# BreaV4B.net
KiCad netlist of a schematic drawn in EAGLE
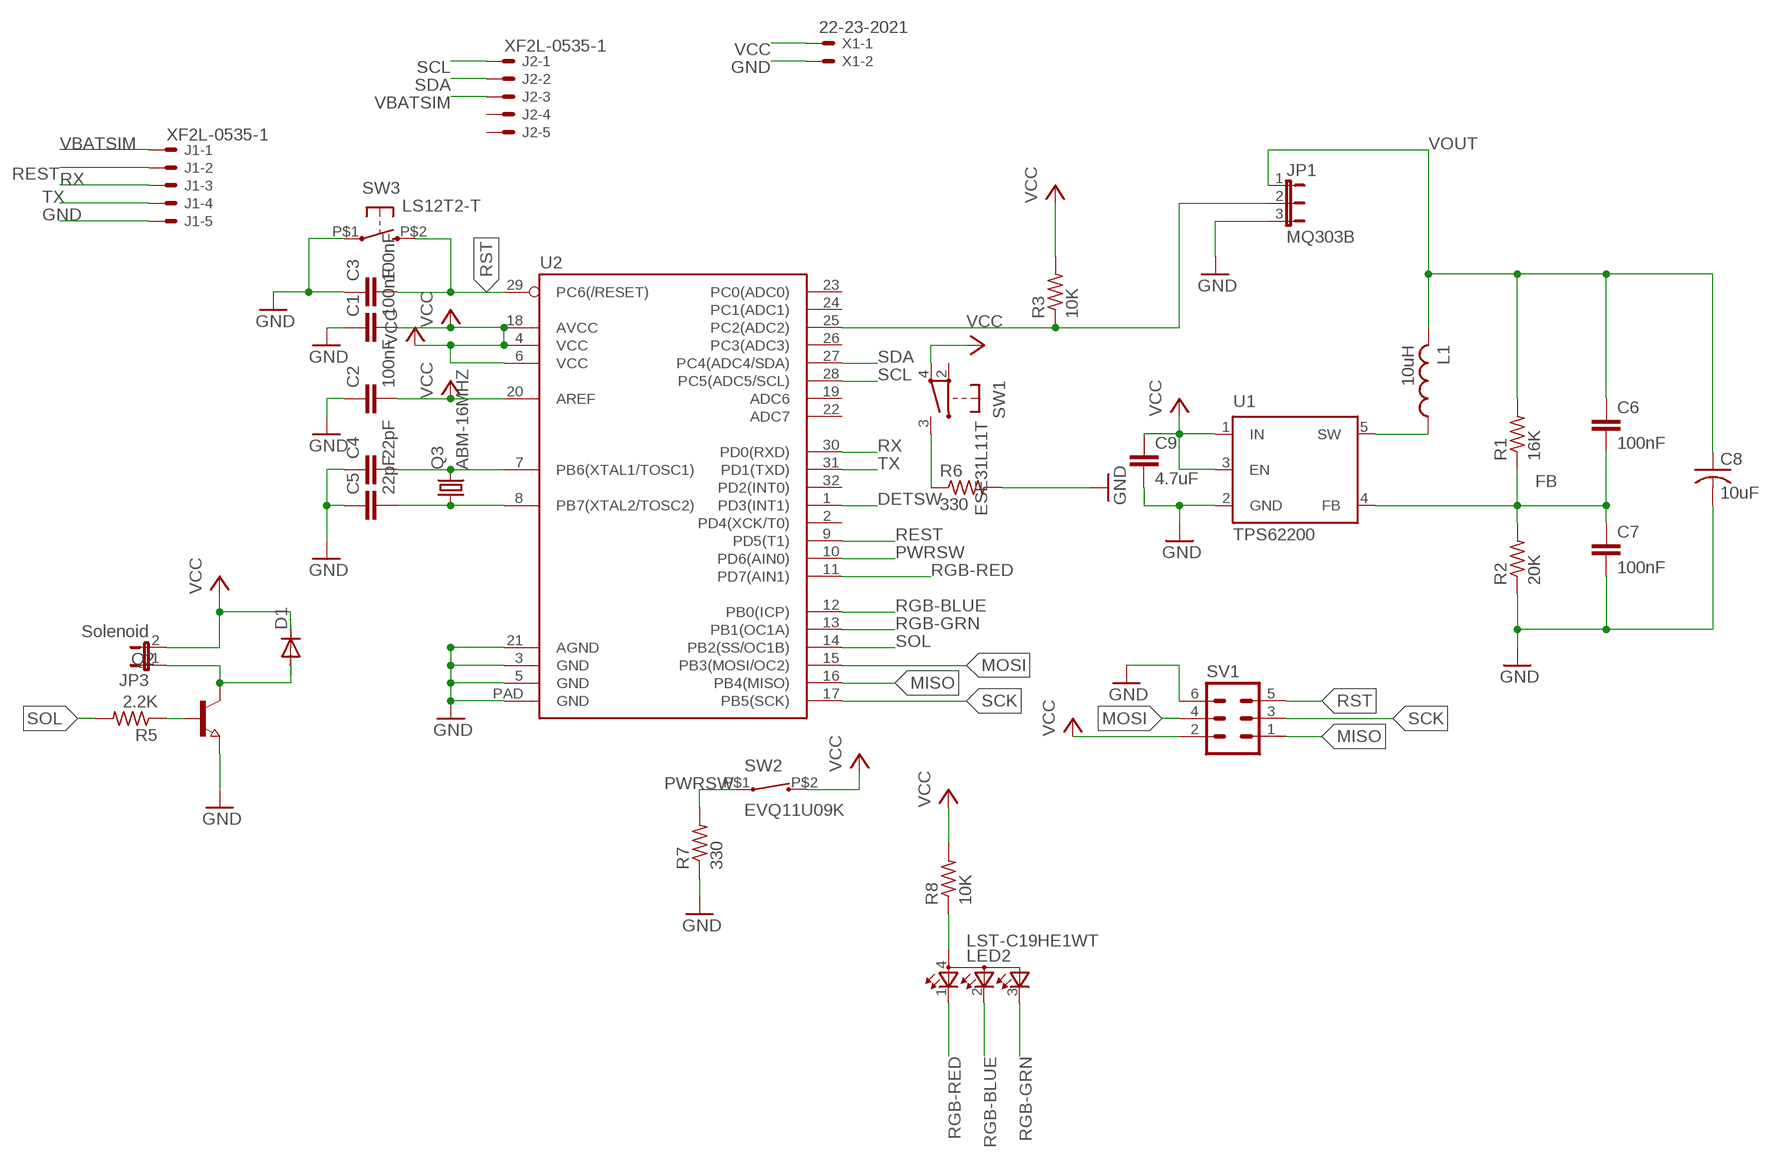
[diagram p0: schematic, sheet 1]

(export (version "E")
  (design (tool "Eeschema 10.0.6"))
  (components
    (comp (ref "C1")
      (value "100nF")
      (footprint "eagle-import:C0603")
      (libsource (lib "eagle-import") (part "C-EUC0603"))
    )
    (comp (ref "C2")
      (value "100nF")
      (footprint "eagle-import:C0603")
      (libsource (lib "eagle-import") (part "C-EUC0603"))
    )
    (comp (ref "C3")
      (value "100nF")
      (footprint "eagle-import:C0603")
      (libsource (lib "eagle-import") (part "C-EUC0603"))
    )
    (comp (ref "C4")
      (value "22pF")
      (footprint "eagle-import:C0603")
      (libsource (lib "eagle-import") (part "C-EUC0603"))
    )
    (comp (ref "C5")
      (value "22pF")
      (footprint "eagle-import:C0603")
      (libsource (lib "eagle-import") (part "C-EUC0603"))
    )
    (comp (ref "C6")
      (value "100nF")
      (footprint "eagle-import:C0402")
      (libsource (lib "eagle-import") (part "C-EUC0402"))
    )
    (comp (ref "C7")
      (value "100nF")
      (footprint "eagle-import:C0402")
      (libsource (lib "eagle-import") (part "C-EUC0402"))
    )
    (comp (ref "C8")
      (value "10uF")
      (footprint "eagle-import:C0805K")
      (libsource (lib "eagle-import") (part "C-USC0805K"))
    )
    (comp (ref "C9")
      (value "4.7uF")
      (footprint "eagle-import:C0402")
      (libsource (lib "eagle-import") (part "C-EUC0402"))
    )
    (comp (ref "D1")
      (value "DIODE-SOD123")
      (footprint "eagle-import:SOD123")
      (libsource (lib "eagle-import") (part "DIODE-SOD123"))
    )
    (comp (ref "J1")
      (value "XF2L-0535-1")
      (footprint "eagle-import:XF2L-0535-1")
      (libsource (lib "eagle-import") (part "XF2-05?35-1L"))
    )
    (comp (ref "J2")
      (value "XF2L-0535-1")
      (footprint "eagle-import:XF2L-0535-1")
      (libsource (lib "eagle-import") (part "XF2-05?35-1L"))
    )
    (comp (ref "JP1")
      (value "MQ303B")
      (footprint "eagle-import:JP2")
      (libsource (lib "eagle-import") (part "JP2E"))
    )
    (comp (ref "JP3")
      (value "Solenoid")
      (footprint "eagle-import:JP1")
      (libsource (lib "eagle-import") (part "JP1E"))
    )
    (comp (ref "L1")
      (value "10uH")
      (footprint "eagle-import:L2825P")
      (libsource (lib "eagle-import") (part "L-USL2825P"))
    )
    (comp (ref "LED2")
      (value "LST-C19HE1WT")
      (footprint "eagle-import:LST-C19HE1WT")
      (libsource (lib "eagle-import") (part "LST-C19HE1WT"))
    )
    (comp (ref "Q2")
      (value "NPN-TRANSISTOR_SOT23")
      (footprint "eagle-import:SOT23")
      (libsource (lib "eagle-import") (part "NPN-TRANSISTOR_SOT23"))
    )
    (comp (ref "Q3")
      (value "ABM-16MHZ")
      (footprint "eagle-import:ABM-16MHZ")
      (libsource (lib "eagle-import") (part "ABM-16MHZ"))
    )
    (comp (ref "R1")
      (value "16K")
      (footprint "eagle-import:R0402")
      (libsource (lib "eagle-import") (part "R-US_R0402"))
    )
    (comp (ref "R2")
      (value "20K")
      (footprint "eagle-import:R0402")
      (libsource (lib "eagle-import") (part "R-US_R0402"))
    )
    (comp (ref "R3")
      (value "10K")
      (footprint "eagle-import:R0402")
      (libsource (lib "eagle-import") (part "R-US_R0402"))
    )
    (comp (ref "R5")
      (value "2.2K")
      (footprint "eagle-import:R0402")
      (libsource (lib "eagle-import") (part "R-US_R0402"))
    )
    (comp (ref "R6")
      (value "330")
      (footprint "eagle-import:R0402")
      (libsource (lib "eagle-import") (part "R-US_R0402"))
    )
    (comp (ref "R7")
      (value "330")
      (footprint "eagle-import:R0402")
      (libsource (lib "eagle-import") (part "R-US_R0402"))
    )
    (comp (ref "R8")
      (value "10K")
      (footprint "eagle-import:R0402")
      (libsource (lib "eagle-import") (part "R-US_R0402"))
    )
    (comp (ref "SV1")
      (value "MA03-2")
      (footprint "eagle-import:MA03-2")
      (libsource (lib "eagle-import") (part "MA03-2"))
    )
    (comp (ref "SW1")
      (value "ESE31L11T")
      (footprint "eagle-import:SWITCH")
      (libsource (lib "eagle-import") (part "ESE31L11T"))
    )
    (comp (ref "SW2")
      (value "EVQ11U09K")
      (footprint "eagle-import:EVQ11U-09K")
      (libsource (lib "eagle-import") (part "EVQ11U09K"))
    )
    (comp (ref "SW3")
      (value "LS12T2-T")
      (footprint "eagle-import:LS12T2-T")
      (libsource (lib "eagle-import") (part "LS12T2-T"))
    )
    (comp (ref "U1")
      (value "TPS62200")
      (footprint "eagle-import:TPS62200")
      (libsource (lib "eagle-import") (part "TPS62200"))
    )
    (comp (ref "U2")
      (value "ATMEGA328P_MLFMLF32")
      (footprint "eagle-import:MLF32-PAD")
      (libsource (lib "eagle-import") (part "ATMEGA328P_MLFMLF32"))
    )
    (comp (ref "X1")
      (value "22-23-2021")
      (footprint "eagle-import:22-23-2021")
      (fields (field (name "MF") "MOLEX"))
      (libsource (lib "eagle-import") (part "22-23-2021"))
    )
  )
  (nets
    (net (code "1") (name "/DETSW") (class "Default")
      (node (ref "R6") (pin "1") (pinfunction "1_1") (pintype "passive"))
      (node (ref "SW1") (pin "3") (pinfunction "1_3") (pintype "passive"))
      (node (ref "U2") (pin "1") (pinfunction "PD3(INT1)_1") (pintype "bidirectional"))
    )
    (net (code "2") (name "/FB") (class "Default")
      (node (ref "C6") (pin "2") (pinfunction "2_2") (pintype "passive"))
      (node (ref "C7") (pin "1") (pinfunction "1_1") (pintype "passive"))
      (node (ref "R1") (pin "1") (pinfunction "1_1") (pintype "passive"))
      (node (ref "R2") (pin "2") (pinfunction "2_2") (pintype "passive"))
      (node (ref "U1") (pin "4") (pinfunction "FB_4") (pintype "passive"))
    )
    (net (code "3") (name "/PWRSW") (class "Default")
      (node (ref "R7") (pin "2") (pinfunction "2_2") (pintype "passive"))
      (node (ref "SW2") (pin "P$1") (pinfunction "1_P$1") (pintype "passive"))
      (node (ref "U2") (pin "10") (pinfunction "PD6(AIN0)_10") (pintype "bidirectional"))
    )
    (net (code "4") (name "/REST") (class "Default")
      (node (ref "J1") (pin "2") (pinfunction "MS_2") (pintype "passive"))
      (node (ref "U2") (pin "9") (pinfunction "PD5(T1)_9") (pintype "bidirectional"))
    )
    (net (code "5") (name "/RGB-BLUE") (class "Default")
      (node (ref "LED2") (pin "2") (pinfunction "CGREEN_2") (pintype "passive"))
      (node (ref "U2") (pin "12") (pinfunction "PB0(ICP)_12") (pintype "bidirectional"))
    )
    (net (code "6") (name "/RGB-GRN") (class "Default")
      (node (ref "LED2") (pin "3") (pinfunction "CBLUE_3") (pintype "passive"))
      (node (ref "U2") (pin "13") (pinfunction "PB1(OC1A)_13") (pintype "bidirectional"))
    )
    (net (code "7") (name "/RGB-RED") (class "Default")
      (node (ref "LED2") (pin "1") (pinfunction "CRED_1") (pintype "passive"))
      (node (ref "U2") (pin "11") (pinfunction "PD7(AIN1)_11") (pintype "bidirectional"))
    )
    (net (code "8") (name "/RX") (class "Default")
      (node (ref "J1") (pin "3") (pinfunction "MS_3") (pintype "passive"))
      (node (ref "U2") (pin "30") (pinfunction "PD0(RXD)_30") (pintype "bidirectional"))
    )
    (net (code "9") (name "/SCL") (class "Default")
      (node (ref "J2") (pin "1") (pinfunction "MSV_1") (pintype "passive"))
      (node (ref "U2") (pin "28") (pinfunction "PC5(ADC5/SCL)_28") (pintype "bidirectional"))
    )
    (net (code "10") (name "/SDA") (class "Default")
      (node (ref "J2") (pin "2") (pinfunction "MS_2") (pintype "passive"))
      (node (ref "U2") (pin "27") (pinfunction "PC4(ADC4/SDA)_27") (pintype "bidirectional"))
    )
    (net (code "11") (name "/TX") (class "Default")
      (node (ref "J1") (pin "4") (pinfunction "MS_4") (pintype "passive"))
      (node (ref "U2") (pin "31") (pinfunction "PD1(TXD)_31") (pintype "bidirectional"))
    )
    (net (code "12") (name "/VBATSIM") (class "Default")
      (node (ref "J1") (pin "1") (pinfunction "MSV_1") (pintype "passive"))
      (node (ref "J2") (pin "3") (pinfunction "MS_3") (pintype "passive"))
    )
    (net (code "13") (name "/VOUT") (class "Default")
      (node (ref "C6") (pin "1") (pinfunction "1_1") (pintype "passive"))
      (node (ref "C8") (pin "1") (pinfunction "1_1") (pintype "passive"))
      (node (ref "JP1") (pin "1") (pinfunction "1_1") (pintype "passive"))
      (node (ref "L1") (pin "2") (pinfunction "2_2") (pintype "passive"))
      (node (ref "R1") (pin "2") (pinfunction "2_2") (pintype "passive"))
    )
    (net (code "14") (name "GND") (class "Default")
      (node (ref "C1") (pin "1") (pinfunction "1_1") (pintype "passive"))
      (node (ref "C2") (pin "1") (pinfunction "1_1") (pintype "passive"))
      (node (ref "C3") (pin "1") (pinfunction "1_1") (pintype "passive"))
      (node (ref "C4") (pin "1") (pinfunction "1_1") (pintype "passive"))
      (node (ref "C5") (pin "1") (pinfunction "1_1") (pintype "passive"))
      (node (ref "C7") (pin "2") (pinfunction "2_2") (pintype "passive"))
      (node (ref "C8") (pin "2") (pinfunction "2_2") (pintype "passive"))
      (node (ref "C9") (pin "2") (pinfunction "2_2") (pintype "passive"))
      (node (ref "J1") (pin "5") (pinfunction "MS_5") (pintype "passive"))
      (node (ref "JP1") (pin "3") (pinfunction "3_3") (pintype "passive"))
      (node (ref "Q2") (pin "2") (pinfunction "E_2") (pintype "passive"))
      (node (ref "R2") (pin "1") (pinfunction "1_1") (pintype "passive"))
      (node (ref "R6") (pin "2") (pinfunction "2_2") (pintype "passive"))
      (node (ref "R7") (pin "1") (pinfunction "1_1") (pintype "passive"))
      (node (ref "SV1") (pin "6") (pinfunction "MISO_6") (pintype "passive"))
      (node (ref "SW3") (pin "P$1") (pinfunction "S1_P$1") (pintype "passive"))
      (node (ref "U1") (pin "2") (pinfunction "GND_2") (pintype "power_in"))
      (node (ref "U2") (pin "21") (pinfunction "AGND_21") (pintype "bidirectional"))
      (node (ref "U2") (pin "3") (pinfunction "GND_3") (pintype "bidirectional"))
      (node (ref "U2") (pin "5") (pinfunction "GND_5") (pintype "bidirectional"))
      (node (ref "U2") (pin "PAD") (pinfunction "GND_PAD") (pintype "bidirectional"))
      (node (ref "X1") (pin "2") (pinfunction "S_2") (pintype "passive"))
    )
    (net (code "15") (name "MISO") (class "Default")
      (node (ref "SV1") (pin "1") (pinfunction "1_1") (pintype "passive"))
      (node (ref "U2") (pin "16") (pinfunction "PB4(MISO)_16") (pintype "bidirectional"))
    )
    (net (code "16") (name "MOSI") (class "Default")
      (node (ref "SV1") (pin "4") (pinfunction "4_4") (pintype "passive"))
      (node (ref "U2") (pin "15") (pinfunction "PB3(MOSI/OC2)_15") (pintype "bidirectional"))
    )
    (net (code "17") (name "Net-(LED2-A)") (class "Default")
      (node (ref "LED2") (pin "4") (pinfunction "A_4") (pintype "passive"))
      (node (ref "R8") (pin "1") (pinfunction "1_1") (pintype "passive"))
    )
    (net (code "18") (name "Net-(Q2-B)") (class "Default")
      (node (ref "Q2") (pin "1") (pinfunction "B_1") (pintype "passive"))
      (node (ref "R5") (pin "1") (pinfunction "1_1") (pintype "passive"))
    )
    (net (code "19") (name "Net-(Q2-C)") (class "Default")
      (node (ref "D1") (pin "A") (pinfunction "A_A") (pintype "passive"))
      (node (ref "JP3") (pin "1") (pinfunction "1_1") (pintype "passive"))
      (node (ref "Q2") (pin "3") (pinfunction "C_3") (pintype "passive"))
    )
    (net (code "20") (name "Net-(Q3-1)") (class "Default")
      (node (ref "C5") (pin "2") (pinfunction "2_2") (pintype "passive"))
      (node (ref "Q3") (pin "P$1") (pinfunction "1_P$1") (pintype "passive"))
      (node (ref "U2") (pin "8") (pinfunction "PB7(XTAL2/TOSC2)_8") (pintype "bidirectional"))
    )
    (net (code "21") (name "Net-(Q3-2)") (class "Default")
      (node (ref "C4") (pin "2") (pinfunction "2_2") (pintype "passive"))
      (node (ref "Q3") (pin "P$2") (pinfunction "2_P$2") (pintype "passive"))
      (node (ref "U2") (pin "7") (pinfunction "PB6(XTAL1/TOSC1)_7") (pintype "bidirectional"))
    )
    (net (code "22") (name "Net-(U1-SW)") (class "Default")
      (node (ref "L1") (pin "1") (pinfunction "1_1") (pintype "passive"))
      (node (ref "U1") (pin "5") (pinfunction "SW_5") (pintype "passive"))
    )
    (net (code "23") (name "Net-(U2-PC2(ADC2))") (class "Default")
      (node (ref "JP1") (pin "2") (pinfunction "2_2") (pintype "passive"))
      (node (ref "R3") (pin "1") (pinfunction "1_1") (pintype "passive"))
      (node (ref "U2") (pin "25") (pinfunction "PC2(ADC2)_25") (pintype "bidirectional"))
    )
    (net (code "24") (name "RST") (class "Default")
      (node (ref "C3") (pin "2") (pinfunction "2_2") (pintype "passive"))
      (node (ref "SV1") (pin "5") (pinfunction "VTG_5") (pintype "passive"))
      (node (ref "SW3") (pin "P$2") (pinfunction "S2_P$2") (pintype "passive"))
      (node (ref "U2") (pin "29") (pinfunction "PC6(/RESET)_29") (pintype "bidirectional"))
    )
    (net (code "25") (name "SCK") (class "Default")
      (node (ref "SV1") (pin "3") (pinfunction "3_3") (pintype "passive"))
      (node (ref "U2") (pin "17") (pinfunction "PB5(SCK)_17") (pintype "bidirectional"))
    )
    (net (code "26") (name "SOL") (class "Default")
      (node (ref "R5") (pin "2") (pinfunction "2_2") (pintype "passive"))
      (node (ref "U2") (pin "14") (pinfunction "PB2(SS/OC1B)_14") (pintype "bidirectional"))
    )
    (net (code "27") (name "VCC") (class "Default")
      (node (ref "C1") (pin "2") (pinfunction "2_2") (pintype "passive"))
      (node (ref "C2") (pin "2") (pinfunction "2_2") (pintype "passive"))
      (node (ref "C9") (pin "1") (pinfunction "1_1") (pintype "passive"))
      (node (ref "D1") (pin "C") (pinfunction "C_C") (pintype "passive"))
      (node (ref "JP3") (pin "2") (pinfunction "2_2") (pintype "passive"))
      (node (ref "R3") (pin "2") (pinfunction "2_2") (pintype "passive"))
      (node (ref "R8") (pin "2") (pinfunction "2_2") (pintype "passive"))
      (node (ref "SV1") (pin "2") (pinfunction "2_2") (pintype "passive"))
      (node (ref "SW1") (pin "4") (pinfunction "C3_4") (pintype "passive"))
      (node (ref "SW2") (pin "P$2") (pinfunction "2_P$2") (pintype "passive"))
      (node (ref "U1") (pin "1") (pinfunction "IN_1") (pintype "input"))
      (node (ref "U1") (pin "3") (pinfunction "EN_3") (pintype "input"))
      (node (ref "U2") (pin "18") (pinfunction "AVCC_18") (pintype "bidirectional"))
      (node (ref "U2") (pin "20") (pinfunction "AREF_20") (pintype "bidirectional"))
      (node (ref "U2") (pin "4") (pinfunction "VCC_4") (pintype "bidirectional"))
      (node (ref "U2") (pin "6") (pinfunction "VCC_6") (pintype "bidirectional"))
      (node (ref "X1") (pin "1") (pinfunction "S_1") (pintype "passive"))
    )
    (net (code "28") (name "unconnected-(J2D-MS-Pad4)") (class "Default")
      (node (ref "J2") (pin "4") (pinfunction "MS_4") (pintype "passive"))
    )
    (net (code "29") (name "unconnected-(J2E-MS-Pad5)") (class "Default")
      (node (ref "J2") (pin "5") (pinfunction "MS_5") (pintype "passive"))
    )
    (net (code "30") (name "unconnected-(SW1-C2-Pad2)") (class "Default")
      (node (ref "SW1") (pin "2") (pinfunction "C2_2") (pintype "passive"))
    )
    (net (code "31") (name "unconnected-(U2-ADC6-Pad19)") (class "Default")
      (node (ref "U2") (pin "19") (pinfunction "ADC6_19") (pintype "bidirectional"))
    )
    (net (code "32") (name "unconnected-(U2-ADC7-Pad22)") (class "Default")
      (node (ref "U2") (pin "22") (pinfunction "ADC7_22") (pintype "bidirectional"))
    )
    (net (code "33") (name "unconnected-(U2-PC0(ADC0)-Pad23)") (class "Default")
      (node (ref "U2") (pin "23") (pinfunction "PC0(ADC0)_23") (pintype "bidirectional"))
    )
    (net (code "34") (name "unconnected-(U2-PC1(ADC1)-Pad24)") (class "Default")
      (node (ref "U2") (pin "24") (pinfunction "PC1(ADC1)_24") (pintype "bidirectional"))
    )
    (net (code "35") (name "unconnected-(U2-PC3(ADC3)-Pad26)") (class "Default")
      (node (ref "U2") (pin "26") (pinfunction "PC3(ADC3)_26") (pintype "bidirectional"))
    )
    (net (code "36") (name "unconnected-(U2-PD2(INT0)-Pad32)") (class "Default")
      (node (ref "U2") (pin "32") (pinfunction "PD2(INT0)_32") (pintype "bidirectional"))
    )
    (net (code "37") (name "unconnected-(U2-PD4(XCK{slash}T0)-Pad2)") (class "Default")
      (node (ref "U2") (pin "2") (pinfunction "PD4(XCK/T0)_2") (pintype "bidirectional"))
    )
  )
)
